# fabflash-mk-2_3-battcon.net
KiCad netlist of a schematic drawn in EAGLE
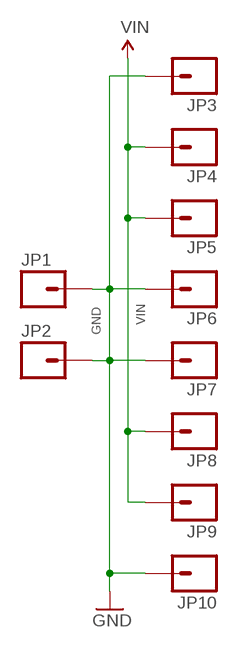
[diagram p0: schematic, sheet 1]

(export (version "E")
  (design (tool "Eeschema 10.0.6"))
  (components
    (comp (ref "JP1")
      (value "M01NOT-A-VIA-NOPE")
      (footprint "eagle-import:1X01_NOSILK_NOSTOP")
      (libsource (lib "eagle-import") (part "M01NOT-A-VIA-NOPE"))
    )
    (comp (ref "JP2")
      (value "M01NOT-A-VIA-NOPE")
      (footprint "eagle-import:1X01_NOSILK_NOSTOP")
      (libsource (lib "eagle-import") (part "M01NOT-A-VIA-NOPE"))
    )
    (comp (ref "JP3")
      (value "M01SMD-1X2.5MM-NS")
      (footprint "eagle-import:1X01-SMD-1X2.5MM-NS")
      (libsource (lib "eagle-import") (part "M01SMD-1X2.5MM-NS"))
    )
    (comp (ref "JP4")
      (value "M01NOSILK-KIT")
      (footprint "eagle-import:1X01NS-KIT")
      (libsource (lib "eagle-import") (part "M01NOSILK-KIT"))
    )
    (comp (ref "JP5")
      (value "M01NOSILK-KIT")
      (footprint "eagle-import:1X01NS-KIT")
      (libsource (lib "eagle-import") (part "M01NOSILK-KIT"))
    )
    (comp (ref "JP6")
      (value "M01SMD-1X2.5MM-NS")
      (footprint "eagle-import:1X01-SMD-1X2.5MM-NS")
      (libsource (lib "eagle-import") (part "M01SMD-1X2.5MM-NS"))
    )
    (comp (ref "JP7")
      (value "M01SMD-1X2.5MM-NS")
      (footprint "eagle-import:1X01-SMD-1X2.5MM-NS")
      (libsource (lib "eagle-import") (part "M01SMD-1X2.5MM-NS"))
    )
    (comp (ref "JP8")
      (value "M01NOSILK-KIT")
      (footprint "eagle-import:1X01NS-KIT")
      (libsource (lib "eagle-import") (part "M01NOSILK-KIT"))
    )
    (comp (ref "JP9")
      (value "M01NOSILK-KIT")
      (footprint "eagle-import:1X01NS-KIT")
      (libsource (lib "eagle-import") (part "M01NOSILK-KIT"))
    )
    (comp (ref "JP10")
      (value "M01SMD-1X2.5MM-NS")
      (footprint "eagle-import:1X01-SMD-1X2.5MM-NS")
      (libsource (lib "eagle-import") (part "M01SMD-1X2.5MM-NS"))
    )
  )
  (nets
    (net (code "1") (name "GND") (class "Default")
      (node (ref "JP1") (pin "P$1") (pinfunction "1_P$1") (pintype "passive"))
      (node (ref "JP10") (pin "1") (pinfunction "1_1") (pintype "passive"))
      (node (ref "JP2") (pin "P$1") (pinfunction "1_P$1") (pintype "passive"))
      (node (ref "JP3") (pin "1") (pinfunction "1_1") (pintype "passive"))
      (node (ref "JP6") (pin "1") (pinfunction "1_1") (pintype "passive"))
      (node (ref "JP7") (pin "1") (pinfunction "1_1") (pintype "passive"))
    )
    (net (code "2") (name "VIN") (class "Default")
      (node (ref "JP4") (pin "1") (pinfunction "1_1") (pintype "passive"))
      (node (ref "JP5") (pin "1") (pinfunction "1_1") (pintype "passive"))
      (node (ref "JP8") (pin "1") (pinfunction "1_1") (pintype "passive"))
      (node (ref "JP9") (pin "1") (pinfunction "1_1") (pintype "passive"))
    )
  )
)
